# 1-Schematic_hub84_board.net
KiCad netlist of a schematic drawn in EasyEDA
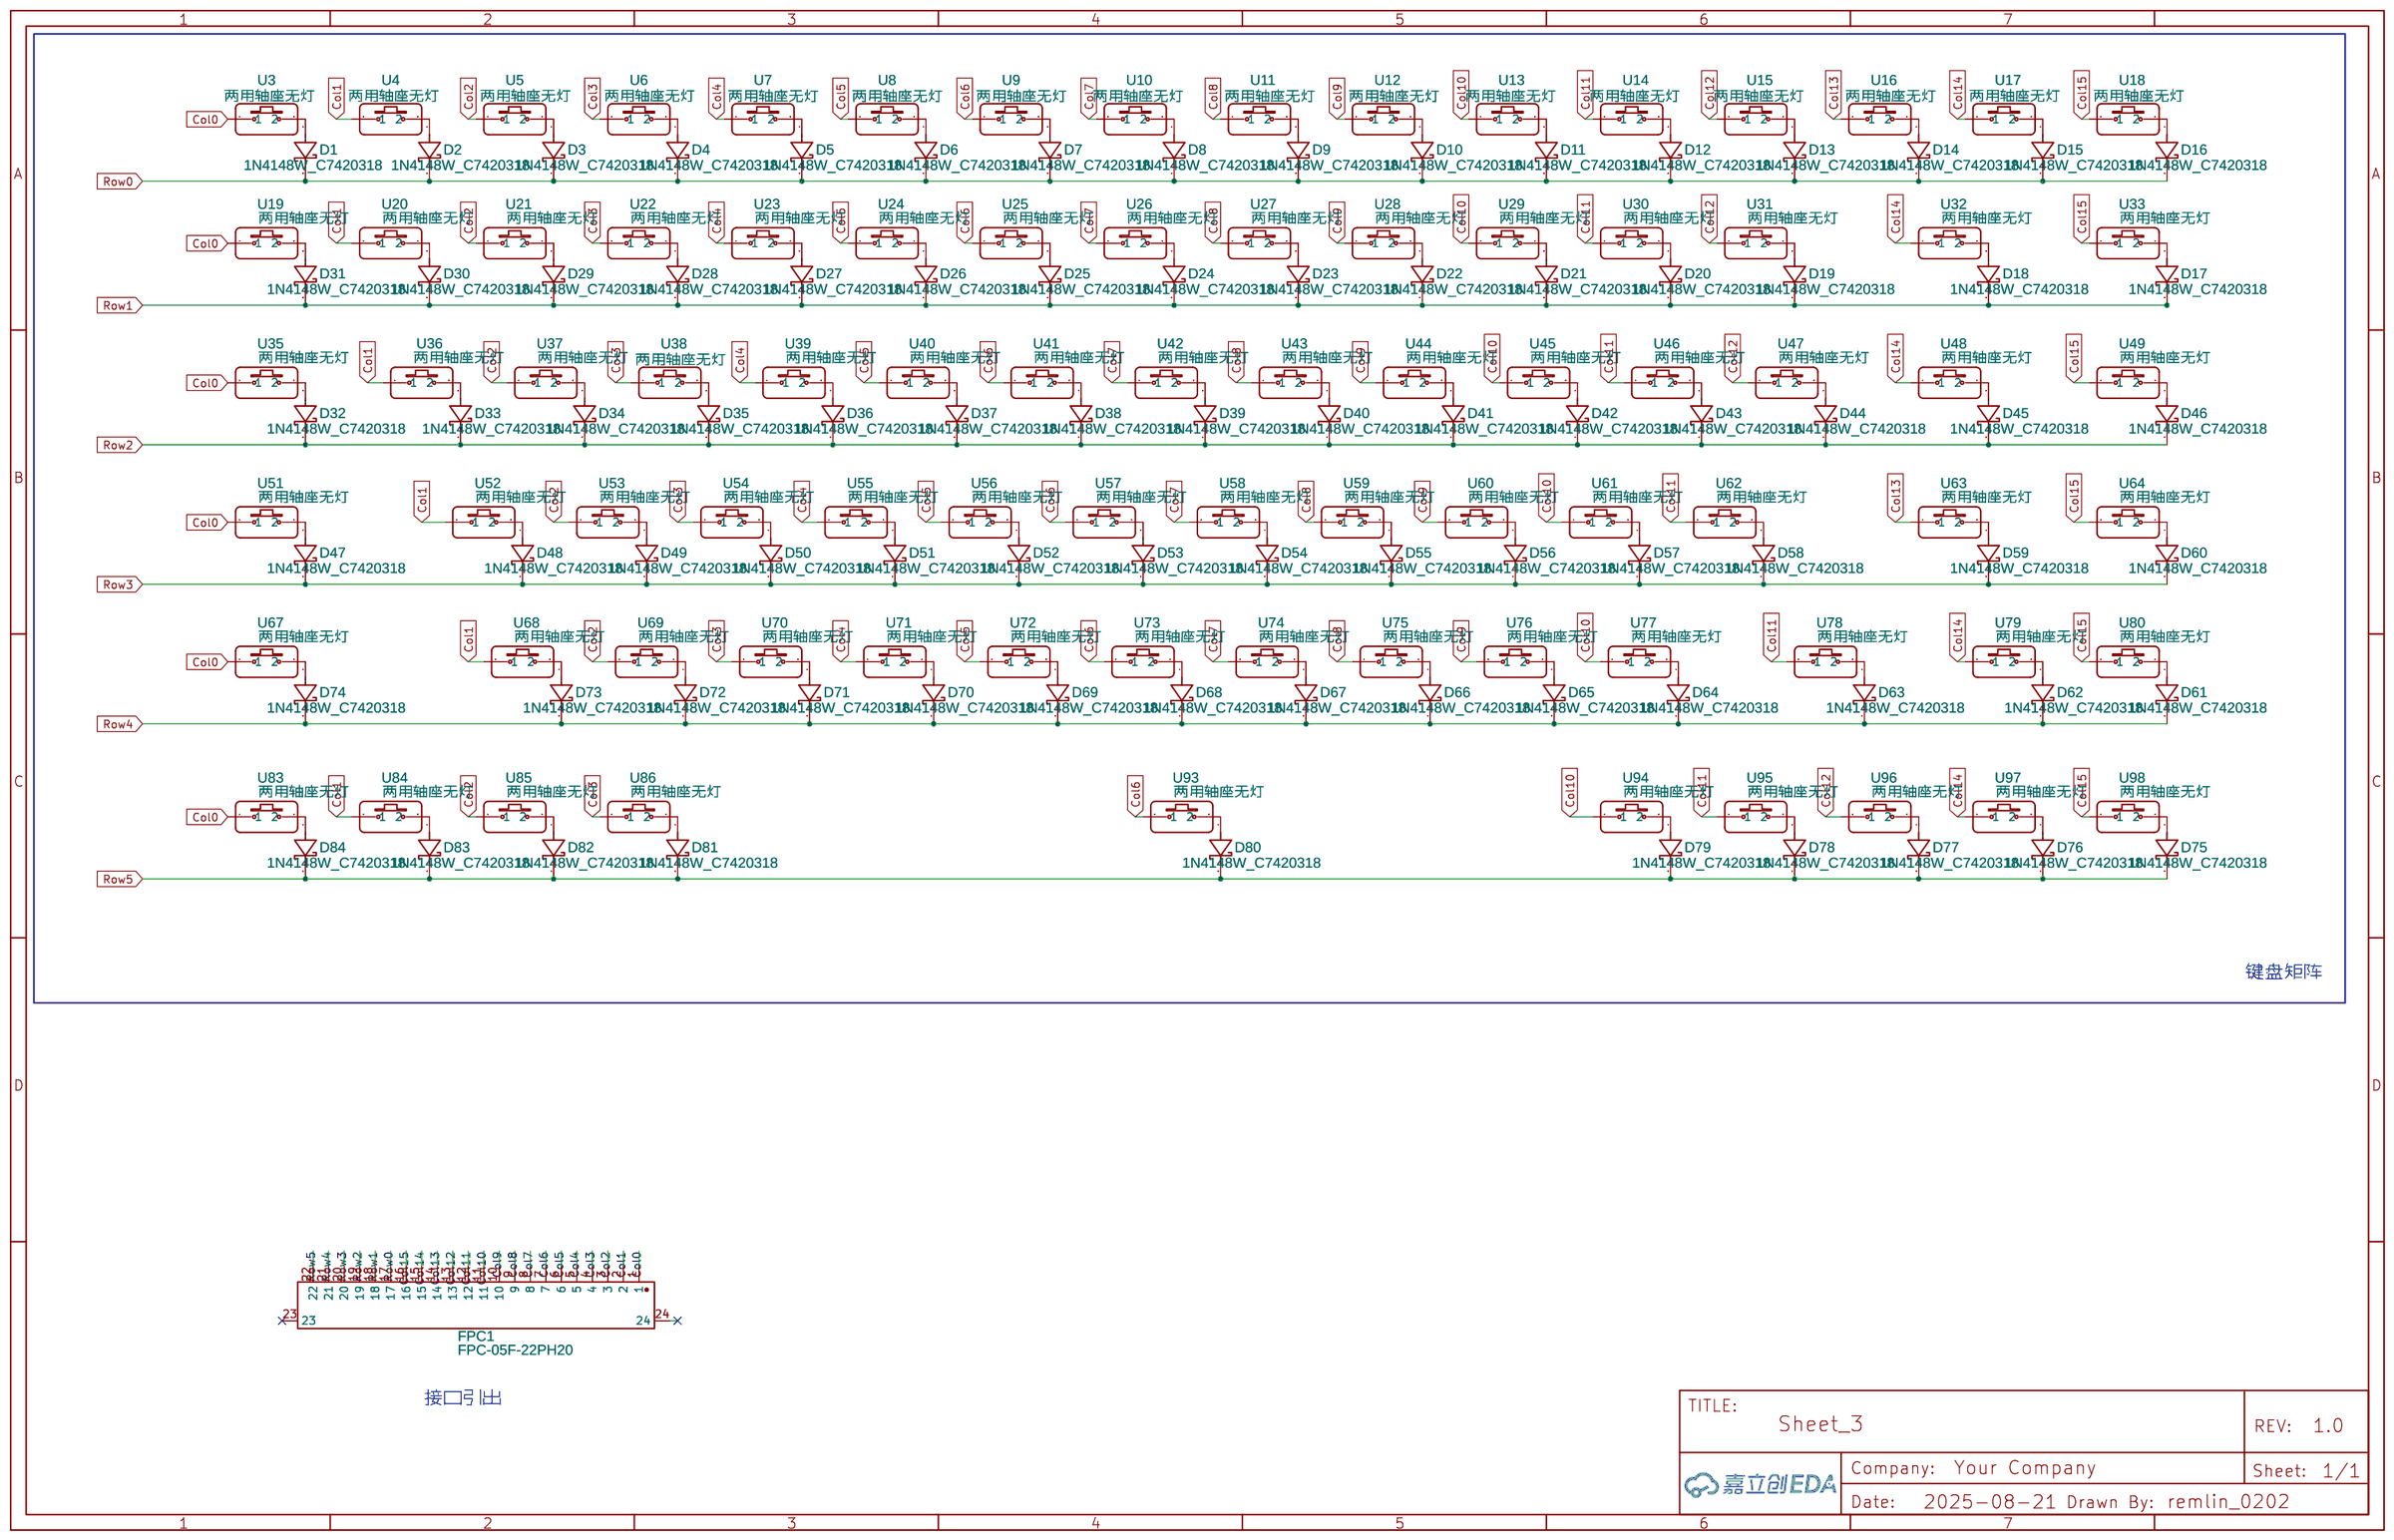
[diagram p0: schematic sheet]

(export (version "E")
  (design (tool "Eeschema 10.0.6"))
  (components
    (comp (ref "D1")
      (value "1N4148W_C7420318")
      (fields (field (name "Manufacturer Part") "1N4148W") (field (name "Manufacturer") "宏嘉诚"))
      (libsource (lib "") (part "1N4148W_C7420318"))
    )
    (comp (ref "D2")
      (value "1N4148W_C7420318")
      (fields (field (name "Manufacturer Part") "1N4148W") (field (name "Manufacturer") "宏嘉诚"))
      (libsource (lib "") (part "1N4148W_C7420318"))
    )
    (comp (ref "D3")
      (value "1N4148W_C7420318")
      (fields (field (name "Manufacturer Part") "1N4148W") (field (name "Manufacturer") "宏嘉诚"))
      (libsource (lib "") (part "1N4148W_C7420318"))
    )
    (comp (ref "D4")
      (value "1N4148W_C7420318")
      (fields (field (name "Manufacturer Part") "1N4148W") (field (name "Manufacturer") "宏嘉诚"))
      (libsource (lib "") (part "1N4148W_C7420318"))
    )
    (comp (ref "D5")
      (value "1N4148W_C7420318")
      (fields (field (name "Manufacturer Part") "1N4148W") (field (name "Manufacturer") "宏嘉诚"))
      (libsource (lib "") (part "1N4148W_C7420318"))
    )
    (comp (ref "D6")
      (value "1N4148W_C7420318")
      (fields (field (name "Manufacturer Part") "1N4148W") (field (name "Manufacturer") "宏嘉诚"))
      (libsource (lib "") (part "1N4148W_C7420318"))
    )
    (comp (ref "D7")
      (value "1N4148W_C7420318")
      (fields (field (name "Manufacturer Part") "1N4148W") (field (name "Manufacturer") "宏嘉诚"))
      (libsource (lib "") (part "1N4148W_C7420318"))
    )
    (comp (ref "D8")
      (value "1N4148W_C7420318")
      (fields (field (name "Manufacturer Part") "1N4148W") (field (name "Manufacturer") "宏嘉诚"))
      (libsource (lib "") (part "1N4148W_C7420318"))
    )
    (comp (ref "D9")
      (value "1N4148W_C7420318")
      (fields (field (name "Manufacturer Part") "1N4148W") (field (name "Manufacturer") "宏嘉诚"))
      (libsource (lib "") (part "1N4148W_C7420318"))
    )
    (comp (ref "D10")
      (value "1N4148W_C7420318")
      (fields (field (name "Manufacturer Part") "1N4148W") (field (name "Manufacturer") "宏嘉诚"))
      (libsource (lib "") (part "1N4148W_C7420318"))
    )
    (comp (ref "D11")
      (value "1N4148W_C7420318")
      (fields (field (name "Manufacturer Part") "1N4148W") (field (name "Manufacturer") "宏嘉诚"))
      (libsource (lib "") (part "1N4148W_C7420318"))
    )
    (comp (ref "D12")
      (value "1N4148W_C7420318")
      (fields (field (name "Manufacturer Part") "1N4148W") (field (name "Manufacturer") "宏嘉诚"))
      (libsource (lib "") (part "1N4148W_C7420318"))
    )
    (comp (ref "D13")
      (value "1N4148W_C7420318")
      (fields (field (name "Manufacturer Part") "1N4148W") (field (name "Manufacturer") "宏嘉诚"))
      (libsource (lib "") (part "1N4148W_C7420318"))
    )
    (comp (ref "D14")
      (value "1N4148W_C7420318")
      (fields (field (name "Manufacturer Part") "1N4148W") (field (name "Manufacturer") "宏嘉诚"))
      (libsource (lib "") (part "1N4148W_C7420318"))
    )
    (comp (ref "D15")
      (value "1N4148W_C7420318")
      (fields (field (name "Manufacturer Part") "1N4148W") (field (name "Manufacturer") "宏嘉诚"))
      (libsource (lib "") (part "1N4148W_C7420318"))
    )
    (comp (ref "D16")
      (value "1N4148W_C7420318")
      (fields (field (name "Manufacturer Part") "1N4148W") (field (name "Manufacturer") "宏嘉诚"))
      (libsource (lib "") (part "1N4148W_C7420318"))
    )
    (comp (ref "D17")
      (value "1N4148W_C7420318")
      (fields (field (name "Manufacturer Part") "1N4148W") (field (name "Manufacturer") "宏嘉诚"))
      (libsource (lib "") (part "1N4148W_C7420318"))
    )
    (comp (ref "D18")
      (value "1N4148W_C7420318")
      (fields (field (name "Manufacturer Part") "1N4148W") (field (name "Manufacturer") "宏嘉诚"))
      (libsource (lib "") (part "1N4148W_C7420318"))
    )
    (comp (ref "D19")
      (value "1N4148W_C7420318")
      (fields (field (name "Manufacturer Part") "1N4148W") (field (name "Manufacturer") "宏嘉诚"))
      (libsource (lib "") (part "1N4148W_C7420318"))
    )
    (comp (ref "D20")
      (value "1N4148W_C7420318")
      (fields (field (name "Manufacturer Part") "1N4148W") (field (name "Manufacturer") "宏嘉诚"))
      (libsource (lib "") (part "1N4148W_C7420318"))
    )
    (comp (ref "D21")
      (value "1N4148W_C7420318")
      (fields (field (name "Manufacturer Part") "1N4148W") (field (name "Manufacturer") "宏嘉诚"))
      (libsource (lib "") (part "1N4148W_C7420318"))
    )
    (comp (ref "D22")
      (value "1N4148W_C7420318")
      (fields (field (name "Manufacturer Part") "1N4148W") (field (name "Manufacturer") "宏嘉诚"))
      (libsource (lib "") (part "1N4148W_C7420318"))
    )
    (comp (ref "D23")
      (value "1N4148W_C7420318")
      (fields (field (name "Manufacturer Part") "1N4148W") (field (name "Manufacturer") "宏嘉诚"))
      (libsource (lib "") (part "1N4148W_C7420318"))
    )
    (comp (ref "D24")
      (value "1N4148W_C7420318")
      (fields (field (name "Manufacturer Part") "1N4148W") (field (name "Manufacturer") "宏嘉诚"))
      (libsource (lib "") (part "1N4148W_C7420318"))
    )
    (comp (ref "D25")
      (value "1N4148W_C7420318")
      (fields (field (name "Manufacturer Part") "1N4148W") (field (name "Manufacturer") "宏嘉诚"))
      (libsource (lib "") (part "1N4148W_C7420318"))
    )
    (comp (ref "D26")
      (value "1N4148W_C7420318")
      (fields (field (name "Manufacturer Part") "1N4148W") (field (name "Manufacturer") "宏嘉诚"))
      (libsource (lib "") (part "1N4148W_C7420318"))
    )
    (comp (ref "D27")
      (value "1N4148W_C7420318")
      (fields (field (name "Manufacturer Part") "1N4148W") (field (name "Manufacturer") "宏嘉诚"))
      (libsource (lib "") (part "1N4148W_C7420318"))
    )
    (comp (ref "D28")
      (value "1N4148W_C7420318")
      (fields (field (name "Manufacturer Part") "1N4148W") (field (name "Manufacturer") "宏嘉诚"))
      (libsource (lib "") (part "1N4148W_C7420318"))
    )
    (comp (ref "D29")
      (value "1N4148W_C7420318")
      (fields (field (name "Manufacturer Part") "1N4148W") (field (name "Manufacturer") "宏嘉诚"))
      (libsource (lib "") (part "1N4148W_C7420318"))
    )
    (comp (ref "D30")
      (value "1N4148W_C7420318")
      (fields (field (name "Manufacturer Part") "1N4148W") (field (name "Manufacturer") "宏嘉诚"))
      (libsource (lib "") (part "1N4148W_C7420318"))
    )
    (comp (ref "D31")
      (value "1N4148W_C7420318")
      (fields (field (name "Manufacturer Part") "1N4148W") (field (name "Manufacturer") "宏嘉诚"))
      (libsource (lib "") (part "1N4148W_C7420318"))
    )
    (comp (ref "D32")
      (value "1N4148W_C7420318")
      (fields (field (name "Manufacturer Part") "1N4148W") (field (name "Manufacturer") "宏嘉诚"))
      (libsource (lib "") (part "1N4148W_C7420318"))
    )
    (comp (ref "D33")
      (value "1N4148W_C7420318")
      (fields (field (name "Manufacturer Part") "1N4148W") (field (name "Manufacturer") "宏嘉诚"))
      (libsource (lib "") (part "1N4148W_C7420318"))
    )
    (comp (ref "D34")
      (value "1N4148W_C7420318")
      (fields (field (name "Manufacturer Part") "1N4148W") (field (name "Manufacturer") "宏嘉诚"))
      (libsource (lib "") (part "1N4148W_C7420318"))
    )
    (comp (ref "D35")
      (value "1N4148W_C7420318")
      (fields (field (name "Manufacturer Part") "1N4148W") (field (name "Manufacturer") "宏嘉诚"))
      (libsource (lib "") (part "1N4148W_C7420318"))
    )
    (comp (ref "D36")
      (value "1N4148W_C7420318")
      (fields (field (name "Manufacturer Part") "1N4148W") (field (name "Manufacturer") "宏嘉诚"))
      (libsource (lib "") (part "1N4148W_C7420318"))
    )
    (comp (ref "D37")
      (value "1N4148W_C7420318")
      (fields (field (name "Manufacturer Part") "1N4148W") (field (name "Manufacturer") "宏嘉诚"))
      (libsource (lib "") (part "1N4148W_C7420318"))
    )
    (comp (ref "D38")
      (value "1N4148W_C7420318")
      (fields (field (name "Manufacturer Part") "1N4148W") (field (name "Manufacturer") "宏嘉诚"))
      (libsource (lib "") (part "1N4148W_C7420318"))
    )
    (comp (ref "D39")
      (value "1N4148W_C7420318")
      (fields (field (name "Manufacturer Part") "1N4148W") (field (name "Manufacturer") "宏嘉诚"))
      (libsource (lib "") (part "1N4148W_C7420318"))
    )
    (comp (ref "D40")
      (value "1N4148W_C7420318")
      (fields (field (name "Manufacturer Part") "1N4148W") (field (name "Manufacturer") "宏嘉诚"))
      (libsource (lib "") (part "1N4148W_C7420318"))
    )
    (comp (ref "D41")
      (value "1N4148W_C7420318")
      (fields (field (name "Manufacturer Part") "1N4148W") (field (name "Manufacturer") "宏嘉诚"))
      (libsource (lib "") (part "1N4148W_C7420318"))
    )
    (comp (ref "D42")
      (value "1N4148W_C7420318")
      (fields (field (name "Manufacturer Part") "1N4148W") (field (name "Manufacturer") "宏嘉诚"))
      (libsource (lib "") (part "1N4148W_C7420318"))
    )
    (comp (ref "D43")
      (value "1N4148W_C7420318")
      (fields (field (name "Manufacturer Part") "1N4148W") (field (name "Manufacturer") "宏嘉诚"))
      (libsource (lib "") (part "1N4148W_C7420318"))
    )
    (comp (ref "D44")
      (value "1N4148W_C7420318")
      (fields (field (name "Manufacturer Part") "1N4148W") (field (name "Manufacturer") "宏嘉诚"))
      (libsource (lib "") (part "1N4148W_C7420318"))
    )
    (comp (ref "D45")
      (value "1N4148W_C7420318")
      (fields (field (name "Manufacturer Part") "1N4148W") (field (name "Manufacturer") "宏嘉诚"))
      (libsource (lib "") (part "1N4148W_C7420318"))
    )
    (comp (ref "D46")
      (value "1N4148W_C7420318")
      (fields (field (name "Manufacturer Part") "1N4148W") (field (name "Manufacturer") "宏嘉诚"))
      (libsource (lib "") (part "1N4148W_C7420318"))
    )
    (comp (ref "D47")
      (value "1N4148W_C7420318")
      (fields (field (name "Manufacturer Part") "1N4148W") (field (name "Manufacturer") "宏嘉诚"))
      (libsource (lib "") (part "1N4148W_C7420318"))
    )
    (comp (ref "D48")
      (value "1N4148W_C7420318")
      (fields (field (name "Manufacturer Part") "1N4148W") (field (name "Manufacturer") "宏嘉诚"))
      (libsource (lib "") (part "1N4148W_C7420318"))
    )
    (comp (ref "D49")
      (value "1N4148W_C7420318")
      (fields (field (name "Manufacturer Part") "1N4148W") (field (name "Manufacturer") "宏嘉诚"))
      (libsource (lib "") (part "1N4148W_C7420318"))
    )
    (comp (ref "D50")
      (value "1N4148W_C7420318")
      (fields (field (name "Manufacturer Part") "1N4148W") (field (name "Manufacturer") "宏嘉诚"))
      (libsource (lib "") (part "1N4148W_C7420318"))
    )
    (comp (ref "D51")
      (value "1N4148W_C7420318")
      (fields (field (name "Manufacturer Part") "1N4148W") (field (name "Manufacturer") "宏嘉诚"))
      (libsource (lib "") (part "1N4148W_C7420318"))
    )
    (comp (ref "D52")
      (value "1N4148W_C7420318")
      (fields (field (name "Manufacturer Part") "1N4148W") (field (name "Manufacturer") "宏嘉诚"))
      (libsource (lib "") (part "1N4148W_C7420318"))
    )
    (comp (ref "D53")
      (value "1N4148W_C7420318")
      (fields (field (name "Manufacturer Part") "1N4148W") (field (name "Manufacturer") "宏嘉诚"))
      (libsource (lib "") (part "1N4148W_C7420318"))
    )
    (comp (ref "D54")
      (value "1N4148W_C7420318")
      (fields (field (name "Manufacturer Part") "1N4148W") (field (name "Manufacturer") "宏嘉诚"))
      (libsource (lib "") (part "1N4148W_C7420318"))
    )
    (comp (ref "D55")
      (value "1N4148W_C7420318")
      (fields (field (name "Manufacturer Part") "1N4148W") (field (name "Manufacturer") "宏嘉诚"))
      (libsource (lib "") (part "1N4148W_C7420318"))
    )
    (comp (ref "D56")
      (value "1N4148W_C7420318")
      (fields (field (name "Manufacturer Part") "1N4148W") (field (name "Manufacturer") "宏嘉诚"))
      (libsource (lib "") (part "1N4148W_C7420318"))
    )
    (comp (ref "D57")
      (value "1N4148W_C7420318")
      (fields (field (name "Manufacturer Part") "1N4148W") (field (name "Manufacturer") "宏嘉诚"))
      (libsource (lib "") (part "1N4148W_C7420318"))
    )
    (comp (ref "D58")
      (value "1N4148W_C7420318")
      (fields (field (name "Manufacturer Part") "1N4148W") (field (name "Manufacturer") "宏嘉诚"))
      (libsource (lib "") (part "1N4148W_C7420318"))
    )
    (comp (ref "D59")
      (value "1N4148W_C7420318")
      (fields (field (name "Manufacturer Part") "1N4148W") (field (name "Manufacturer") "宏嘉诚"))
      (libsource (lib "") (part "1N4148W_C7420318"))
    )
    (comp (ref "D60")
      (value "1N4148W_C7420318")
      (fields (field (name "Manufacturer Part") "1N4148W") (field (name "Manufacturer") "宏嘉诚"))
      (libsource (lib "") (part "1N4148W_C7420318"))
    )
    (comp (ref "D61")
      (value "1N4148W_C7420318")
      (fields (field (name "Manufacturer Part") "1N4148W") (field (name "Manufacturer") "宏嘉诚"))
      (libsource (lib "") (part "1N4148W_C7420318"))
    )
    (comp (ref "D62")
      (value "1N4148W_C7420318")
      (fields (field (name "Manufacturer Part") "1N4148W") (field (name "Manufacturer") "宏嘉诚"))
      (libsource (lib "") (part "1N4148W_C7420318"))
    )
    (comp (ref "D63")
      (value "1N4148W_C7420318")
      (fields (field (name "Manufacturer Part") "1N4148W") (field (name "Manufacturer") "宏嘉诚"))
      (libsource (lib "") (part "1N4148W_C7420318"))
    )
    (comp (ref "D64")
      (value "1N4148W_C7420318")
      (fields (field (name "Manufacturer Part") "1N4148W") (field (name "Manufacturer") "宏嘉诚"))
      (libsource (lib "") (part "1N4148W_C7420318"))
    )
    (comp (ref "D65")
      (value "1N4148W_C7420318")
      (fields (field (name "Manufacturer Part") "1N4148W") (field (name "Manufacturer") "宏嘉诚"))
      (libsource (lib "") (part "1N4148W_C7420318"))
    )
    (comp (ref "D66")
      (value "1N4148W_C7420318")
      (fields (field (name "Manufacturer Part") "1N4148W") (field (name "Manufacturer") "宏嘉诚"))
      (libsource (lib "") (part "1N4148W_C7420318"))
    )
    (comp (ref "D67")
      (value "1N4148W_C7420318")
      (fields (field (name "Manufacturer Part") "1N4148W") (field (name "Manufacturer") "宏嘉诚"))
      (libsource (lib "") (part "1N4148W_C7420318"))
    )
    (comp (ref "D68")
      (value "1N4148W_C7420318")
      (fields (field (name "Manufacturer Part") "1N4148W") (field (name "Manufacturer") "宏嘉诚"))
      (libsource (lib "") (part "1N4148W_C7420318"))
    )
    (comp (ref "D69")
      (value "1N4148W_C7420318")
      (fields (field (name "Manufacturer Part") "1N4148W") (field (name "Manufacturer") "宏嘉诚"))
      (libsource (lib "") (part "1N4148W_C7420318"))
    )
    (comp (ref "D70")
      (value "1N4148W_C7420318")
      (fields (field (name "Manufacturer Part") "1N4148W") (field (name "Manufacturer") "宏嘉诚"))
      (libsource (lib "") (part "1N4148W_C7420318"))
    )
    (comp (ref "D71")
      (value "1N4148W_C7420318")
      (fields (field (name "Manufacturer Part") "1N4148W") (field (name "Manufacturer") "宏嘉诚"))
      (libsource (lib "") (part "1N4148W_C7420318"))
    )
    (comp (ref "D72")
      (value "1N4148W_C7420318")
      (fields (field (name "Manufacturer Part") "1N4148W") (field (name "Manufacturer") "宏嘉诚"))
      (libsource (lib "") (part "1N4148W_C7420318"))
    )
    (comp (ref "D73")
      (value "1N4148W_C7420318")
      (fields (field (name "Manufacturer Part") "1N4148W") (field (name "Manufacturer") "宏嘉诚"))
      (libsource (lib "") (part "1N4148W_C7420318"))
    )
    (comp (ref "D74")
      (value "1N4148W_C7420318")
      (fields (field (name "Manufacturer Part") "1N4148W") (field (name "Manufacturer") "宏嘉诚"))
      (libsource (lib "") (part "1N4148W_C7420318"))
    )
    (comp (ref "D75")
      (value "1N4148W_C7420318")
      (fields (field (name "Manufacturer Part") "1N4148W") (field (name "Manufacturer") "宏嘉诚"))
      (libsource (lib "") (part "1N4148W_C7420318"))
    )
    (comp (ref "D76")
      (value "1N4148W_C7420318")
      (fields (field (name "Manufacturer Part") "1N4148W") (field (name "Manufacturer") "宏嘉诚"))
      (libsource (lib "") (part "1N4148W_C7420318"))
    )
    (comp (ref "D77")
      (value "1N4148W_C7420318")
      (fields (field (name "Manufacturer Part") "1N4148W") (field (name "Manufacturer") "宏嘉诚"))
      (libsource (lib "") (part "1N4148W_C7420318"))
    )
    (comp (ref "D78")
      (value "1N4148W_C7420318")
      (fields (field (name "Manufacturer Part") "1N4148W") (field (name "Manufacturer") "宏嘉诚"))
      (libsource (lib "") (part "1N4148W_C7420318"))
    )
    (comp (ref "D79")
      (value "1N4148W_C7420318")
      (fields (field (name "Manufacturer Part") "1N4148W") (field (name "Manufacturer") "宏嘉诚"))
      (libsource (lib "") (part "1N4148W_C7420318"))
    )
    (comp (ref "D80")
      (value "1N4148W_C7420318")
      (fields (field (name "Manufacturer Part") "1N4148W") (field (name "Manufacturer") "宏嘉诚"))
      (libsource (lib "") (part "1N4148W_C7420318"))
    )
    (comp (ref "D81")
      (value "1N4148W_C7420318")
      (fields (field (name "Manufacturer Part") "1N4148W") (field (name "Manufacturer") "宏嘉诚"))
      (libsource (lib "") (part "1N4148W_C7420318"))
    )
    (comp (ref "D82")
      (value "1N4148W_C7420318")
      (fields (field (name "Manufacturer Part") "1N4148W") (field (name "Manufacturer") "宏嘉诚"))
      (libsource (lib "") (part "1N4148W_C7420318"))
    )
    (comp (ref "D83")
      (value "1N4148W_C7420318")
      (fields (field (name "Manufacturer Part") "1N4148W") (field (name "Manufacturer") "宏嘉诚"))
      (libsource (lib "") (part "1N4148W_C7420318"))
    )
    (comp (ref "D84")
      (value "1N4148W_C7420318")
      (fields (field (name "Manufacturer Part") "1N4148W") (field (name "Manufacturer") "宏嘉诚"))
      (libsource (lib "") (part "1N4148W_C7420318"))
    )
    (comp (ref "FPC1")
      (value "FPC-05F-22PH20")
      (fields (field (name "Manufacturer") "XUNPU(讯普)"))
      (libsource (lib "") (part "FPC-05F-22PH20"))
    )
    (comp (ref "U3") (value "两用轴座无灯") (libsource (lib "") (part "两用轴座无灯")))
    (comp (ref "U4") (value "两用轴座无灯") (libsource (lib "") (part "两用轴座无灯")))
    (comp (ref "U5") (value "两用轴座无灯") (libsource (lib "") (part "两用轴座无灯")))
    (comp (ref "U6") (value "两用轴座无灯") (libsource (lib "") (part "两用轴座无灯")))
    (comp (ref "U7") (value "两用轴座无灯") (libsource (lib "") (part "两用轴座无灯")))
    (comp (ref "U8") (value "两用轴座无灯") (libsource (lib "") (part "两用轴座无灯")))
    (comp (ref "U9") (value "两用轴座无灯") (libsource (lib "") (part "两用轴座无灯")))
    (comp (ref "U10") (value "两用轴座无灯") (libsource (lib "") (part "两用轴座无灯")))
    (comp (ref "U11") (value "两用轴座无灯") (libsource (lib "") (part "两用轴座无灯")))
    (comp (ref "U12") (value "两用轴座无灯") (libsource (lib "") (part "两用轴座无灯")))
    (comp (ref "U13") (value "两用轴座无灯") (libsource (lib "") (part "两用轴座无灯")))
    (comp (ref "U14") (value "两用轴座无灯") (libsource (lib "") (part "两用轴座无灯")))
    (comp (ref "U15") (value "两用轴座无灯") (libsource (lib "") (part "两用轴座无灯")))
    (comp (ref "U16") (value "两用轴座无灯") (libsource (lib "") (part "两用轴座无灯")))
    (comp (ref "U17") (value "两用轴座无灯") (libsource (lib "") (part "两用轴座无灯")))
    (comp (ref "U18") (value "两用轴座无灯") (libsource (lib "") (part "两用轴座无灯")))
    (comp (ref "U19") (value "两用轴座无灯") (libsource (lib "") (part "两用轴座无灯")))
    (comp (ref "U20") (value "两用轴座无灯") (libsource (lib "") (part "两用轴座无灯")))
    (comp (ref "U21") (value "两用轴座无灯") (libsource (lib "") (part "两用轴座无灯")))
    (comp (ref "U22") (value "两用轴座无灯") (libsource (lib "") (part "两用轴座无灯")))
    (comp (ref "U23") (value "两用轴座无灯") (libsource (lib "") (part "两用轴座无灯")))
    (comp (ref "U24") (value "两用轴座无灯") (libsource (lib "") (part "两用轴座无灯")))
    (comp (ref "U25") (value "两用轴座无灯") (libsource (lib "") (part "两用轴座无灯")))
    (comp (ref "U26") (value "两用轴座无灯") (libsource (lib "") (part "两用轴座无灯")))
    (comp (ref "U27") (value "两用轴座无灯") (libsource (lib "") (part "两用轴座无灯")))
    (comp (ref "U28") (value "两用轴座无灯") (libsource (lib "") (part "两用轴座无灯")))
    (comp (ref "U29") (value "两用轴座无灯") (libsource (lib "") (part "两用轴座无灯")))
    (comp (ref "U30") (value "两用轴座无灯") (libsource (lib "") (part "两用轴座无灯")))
    (comp (ref "U31") (value "两用轴座无灯") (libsource (lib "") (part "两用轴座无灯")))
    (comp (ref "U32") (value "两用轴座无灯") (libsource (lib "") (part "两用轴座无灯")))
    (comp (ref "U33") (value "两用轴座无灯") (libsource (lib "") (part "两用轴座无灯")))
    (comp (ref "U35") (value "两用轴座无灯") (libsource (lib "") (part "两用轴座无灯")))
    (comp (ref "U36") (value "两用轴座无灯") (libsource (lib "") (part "两用轴座无灯")))
    (comp (ref "U37") (value "两用轴座无灯") (libsource (lib "") (part "两用轴座无灯")))
    (comp (ref "U38") (value "两用轴座无灯") (libsource (lib "") (part "两用轴座无灯")))
    (comp (ref "U39") (value "两用轴座无灯") (libsource (lib "") (part "两用轴座无灯")))
    (comp (ref "U40") (value "两用轴座无灯") (libsource (lib "") (part "两用轴座无灯")))
    (comp (ref "U41") (value "两用轴座无灯") (libsource (lib "") (part "两用轴座无灯")))
    (comp (ref "U42") (value "两用轴座无灯") (libsource (lib "") (part "两用轴座无灯")))
    (comp (ref "U43") (value "两用轴座无灯") (libsource (lib "") (part "两用轴座无灯")))
    (comp (ref "U44") (value "两用轴座无灯") (libsource (lib "") (part "两用轴座无灯")))
    (comp (ref "U45") (value "两用轴座无灯") (libsource (lib "") (part "两用轴座无灯")))
    (comp (ref "U46") (value "两用轴座无灯") (libsource (lib "") (part "两用轴座无灯")))
    (comp (ref "U47") (value "两用轴座无灯") (libsource (lib "") (part "两用轴座无灯")))
    (comp (ref "U48") (value "两用轴座无灯") (libsource (lib "") (part "两用轴座无灯")))
    (comp (ref "U49") (value "两用轴座无灯") (libsource (lib "") (part "两用轴座无灯")))
    (comp (ref "U51") (value "两用轴座无灯") (libsource (lib "") (part "两用轴座无灯")))
    (comp (ref "U52") (value "两用轴座无灯") (libsource (lib "") (part "两用轴座无灯")))
    (comp (ref "U53") (value "两用轴座无灯") (libsource (lib "") (part "两用轴座无灯")))
    (comp (ref "U54") (value "两用轴座无灯") (libsource (lib "") (part "两用轴座无灯")))
    (comp (ref "U55") (value "两用轴座无灯") (libsource (lib "") (part "两用轴座无灯")))
    (comp (ref "U56") (value "两用轴座无灯") (libsource (lib "") (part "两用轴座无灯")))
    (comp (ref "U57") (value "两用轴座无灯") (libsource (lib "") (part "两用轴座无灯")))
    (comp (ref "U58") (value "两用轴座无灯") (libsource (lib "") (part "两用轴座无灯")))
    (comp (ref "U59") (value "两用轴座无灯") (libsource (lib "") (part "两用轴座无灯")))
    (comp (ref "U60") (value "两用轴座无灯") (libsource (lib "") (part "两用轴座无灯")))
    (comp (ref "U61") (value "两用轴座无灯") (libsource (lib "") (part "两用轴座无灯")))
    (comp (ref "U62") (value "两用轴座无灯") (libsource (lib "") (part "两用轴座无灯")))
    (comp (ref "U63") (value "两用轴座无灯") (libsource (lib "") (part "两用轴座无灯")))
    (comp (ref "U64") (value "两用轴座无灯") (libsource (lib "") (part "两用轴座无灯")))
    (comp (ref "U67") (value "两用轴座无灯") (libsource (lib "") (part "两用轴座无灯")))
    (comp (ref "U68") (value "两用轴座无灯") (libsource (lib "") (part "两用轴座无灯")))
    (comp (ref "U69") (value "两用轴座无灯") (libsource (lib "") (part "两用轴座无灯")))
    (comp (ref "U70") (value "两用轴座无灯") (libsource (lib "") (part "两用轴座无灯")))
    (comp (ref "U71") (value "两用轴座无灯") (libsource (lib "") (part "两用轴座无灯")))
    (comp (ref "U72") (value "两用轴座无灯") (libsource (lib "") (part "两用轴座无灯")))
    (comp (ref "U73") (value "两用轴座无灯") (libsource (lib "") (part "两用轴座无灯")))
    (comp (ref "U74") (value "两用轴座无灯") (libsource (lib "") (part "两用轴座无灯")))
    (comp (ref "U75") (value "两用轴座无灯") (libsource (lib "") (part "两用轴座无灯")))
    (comp (ref "U76") (value "两用轴座无灯") (libsource (lib "") (part "两用轴座无灯")))
    (comp (ref "U77") (value "两用轴座无灯") (libsource (lib "") (part "两用轴座无灯")))
    (comp (ref "U78") (value "两用轴座无灯") (libsource (lib "") (part "两用轴座无灯")))
    (comp (ref "U79") (value "两用轴座无灯") (libsource (lib "") (part "两用轴座无灯")))
    (comp (ref "U80") (value "两用轴座无灯") (libsource (lib "") (part "两用轴座无灯")))
    (comp (ref "U83") (value "两用轴座无灯") (libsource (lib "") (part "两用轴座无灯")))
    (comp (ref "U84") (value "两用轴座无灯") (libsource (lib "") (part "两用轴座无灯")))
    (comp (ref "U85") (value "两用轴座无灯") (libsource (lib "") (part "两用轴座无灯")))
    (comp (ref "U86") (value "两用轴座无灯") (libsource (lib "") (part "两用轴座无灯")))
    (comp (ref "U93") (value "两用轴座无灯") (libsource (lib "") (part "两用轴座无灯")))
    (comp (ref "U94") (value "两用轴座无灯") (libsource (lib "") (part "两用轴座无灯")))
    (comp (ref "U95") (value "两用轴座无灯") (libsource (lib "") (part "两用轴座无灯")))
    (comp (ref "U96") (value "两用轴座无灯") (libsource (lib "") (part "两用轴座无灯")))
    (comp (ref "U97") (value "两用轴座无灯") (libsource (lib "") (part "两用轴座无灯")))
    (comp (ref "U98") (value "两用轴座无灯") (libsource (lib "") (part "两用轴座无灯")))
  )
  (nets
    (net (code "1") (name "Col0") (class "Default")
      (node (ref "FPC1") (pin "1") (pinfunction "1_1") (pintype "unspecified"))
      (node (ref "U19") (pin "1") (pinfunction "1_1") (pintype "unspecified"))
      (node (ref "U3") (pin "1") (pinfunction "1_1") (pintype "unspecified"))
      (node (ref "U35") (pin "1") (pinfunction "1_1") (pintype "unspecified"))
      (node (ref "U51") (pin "1") (pinfunction "1_1") (pintype "unspecified"))
      (node (ref "U67") (pin "1") (pinfunction "1_1") (pintype "unspecified"))
      (node (ref "U83") (pin "1") (pinfunction "1_1") (pintype "unspecified"))
    )
    (net (code "2") (name "Col1") (class "Default")
      (node (ref "FPC1") (pin "2") (pinfunction "2_2") (pintype "unspecified"))
      (node (ref "U20") (pin "1") (pinfunction "1_1") (pintype "unspecified"))
      (node (ref "U36") (pin "1") (pinfunction "1_1") (pintype "unspecified"))
      (node (ref "U4") (pin "1") (pinfunction "1_1") (pintype "unspecified"))
      (node (ref "U52") (pin "1") (pinfunction "1_1") (pintype "unspecified"))
      (node (ref "U68") (pin "1") (pinfunction "1_1") (pintype "unspecified"))
      (node (ref "U84") (pin "1") (pinfunction "1_1") (pintype "unspecified"))
    )
    (net (code "3") (name "Col2") (class "Default")
      (node (ref "FPC1") (pin "3") (pinfunction "3_3") (pintype "unspecified"))
      (node (ref "U21") (pin "1") (pinfunction "1_1") (pintype "unspecified"))
      (node (ref "U37") (pin "1") (pinfunction "1_1") (pintype "unspecified"))
      (node (ref "U5") (pin "1") (pinfunction "1_1") (pintype "unspecified"))
      (node (ref "U53") (pin "1") (pinfunction "1_1") (pintype "unspecified"))
      (node (ref "U69") (pin "1") (pinfunction "1_1") (pintype "unspecified"))
      (node (ref "U85") (pin "1") (pinfunction "1_1") (pintype "unspecified"))
    )
    (net (code "4") (name "Col3") (class "Default")
      (node (ref "FPC1") (pin "4") (pinfunction "4_4") (pintype "unspecified"))
      (node (ref "U22") (pin "1") (pinfunction "1_1") (pintype "unspecified"))
      (node (ref "U38") (pin "1") (pinfunction "1_1") (pintype "unspecified"))
      (node (ref "U54") (pin "1") (pinfunction "1_1") (pintype "unspecified"))
      (node (ref "U6") (pin "1") (pinfunction "1_1") (pintype "unspecified"))
      (node (ref "U70") (pin "1") (pinfunction "1_1") (pintype "unspecified"))
      (node (ref "U86") (pin "1") (pinfunction "1_1") (pintype "unspecified"))
    )
    (net (code "5") (name "Col4") (class "Default")
      (node (ref "FPC1") (pin "5") (pinfunction "5_5") (pintype "unspecified"))
      (node (ref "U23") (pin "1") (pinfunction "1_1") (pintype "unspecified"))
      (node (ref "U39") (pin "1") (pinfunction "1_1") (pintype "unspecified"))
      (node (ref "U55") (pin "1") (pinfunction "1_1") (pintype "unspecified"))
      (node (ref "U7") (pin "1") (pinfunction "1_1") (pintype "unspecified"))
      (node (ref "U71") (pin "1") (pinfunction "1_1") (pintype "unspecified"))
    )
    (net (code "6") (name "Col5") (class "Default")
      (node (ref "FPC1") (pin "6") (pinfunction "6_6") (pintype "unspecified"))
      (node (ref "U24") (pin "1") (pinfunction "1_1") (pintype "unspecified"))
      (node (ref "U40") (pin "1") (pinfunction "1_1") (pintype "unspecified"))
      (node (ref "U56") (pin "1") (pinfunction "1_1") (pintype "unspecified"))
      (node (ref "U72") (pin "1") (pinfunction "1_1") (pintype "unspecified"))
      (node (ref "U8") (pin "1") (pinfunction "1_1") (pintype "unspecified"))
    )
    (net (code "7") (name "Col6") (class "Default")
      (node (ref "FPC1") (pin "7") (pinfunction "7_7") (pintype "unspecified"))
      (node (ref "U25") (pin "1") (pinfunction "1_1") (pintype "unspecified"))
      (node (ref "U41") (pin "1") (pinfunction "1_1") (pintype "unspecified"))
      (node (ref "U57") (pin "1") (pinfunction "1_1") (pintype "unspecified"))
      (node (ref "U73") (pin "1") (pinfunction "1_1") (pintype "unspecified"))
      (node (ref "U9") (pin "1") (pinfunction "1_1") (pintype "unspecified"))
      (node (ref "U93") (pin "1") (pinfunction "1_1") (pintype "unspecified"))
    )
    (net (code "8") (name "Col7") (class "Default")
      (node (ref "FPC1") (pin "8") (pinfunction "8_8") (pintype "unspecified"))
      (node (ref "U10") (pin "1") (pinfunction "1_1") (pintype "unspecified"))
      (node (ref "U26") (pin "1") (pinfunction "1_1") (pintype "unspecified"))
      (node (ref "U42") (pin "1") (pinfunction "1_1") (pintype "unspecified"))
      (node (ref "U58") (pin "1") (pinfunction "1_1") (pintype "unspecified"))
      (node (ref "U74") (pin "1") (pinfunction "1_1") (pintype "unspecified"))
    )
    (net (code "9") (name "Col8") (class "Default")
      (node (ref "FPC1") (pin "9") (pinfunction "9_9") (pintype "unspecified"))
      (node (ref "U11") (pin "1") (pinfunction "1_1") (pintype "unspecified"))
      (node (ref "U27") (pin "1") (pinfunction "1_1") (pintype "unspecified"))
      (node (ref "U43") (pin "1") (pinfunction "1_1") (pintype "unspecified"))
      (node (ref "U59") (pin "1") (pinfunction "1_1") (pintype "unspecified"))
      (node (ref "U75") (pin "1") (pinfunction "1_1") (pintype "unspecified"))
    )
    (net (code "10") (name "Col9") (class "Default")
      (node (ref "FPC1") (pin "10") (pinfunction "10_10") (pintype "unspecified"))
      (node (ref "U12") (pin "1") (pinfunction "1_1") (pintype "unspecified"))
      (node (ref "U28") (pin "1") (pinfunction "1_1") (pintype "unspecified"))
      (node (ref "U44") (pin "1") (pinfunction "1_1") (pintype "unspecified"))
      (node (ref "U60") (pin "1") (pinfunction "1_1") (pintype "unspecified"))
      (node (ref "U76") (pin "1") (pinfunction "1_1") (pintype "unspecified"))
    )
    (net (code "11") (name "Col10") (class "Default")
      (node (ref "FPC1") (pin "11") (pinfunction "11_11") (pintype "unspecified"))
      (node (ref "U13") (pin "1") (pinfunction "1_1") (pintype "unspecified"))
      (node (ref "U29") (pin "1") (pinfunction "1_1") (pintype "unspecified"))
      (node (ref "U45") (pin "1") (pinfunction "1_1") (pintype "unspecified"))
      (node (ref "U61") (pin "1") (pinfunction "1_1") (pintype "unspecified"))
      (node (ref "U77") (pin "1") (pinfunction "1_1") (pintype "unspecified"))
      (node (ref "U94") (pin "1") (pinfunction "1_1") (pintype "unspecified"))
    )
    (net (code "12") (name "Col11") (class "Default")
      (node (ref "FPC1") (pin "12") (pinfunction "12_12") (pintype "unspecified"))
      (node (ref "U14") (pin "1") (pinfunction "1_1") (pintype "unspecified"))
      (node (ref "U30") (pin "1") (pinfunction "1_1") (pintype "unspecified"))
      (node (ref "U46") (pin "1") (pinfunction "1_1") (pintype "unspecified"))
      (node (ref "U62") (pin "1") (pinfunction "1_1") (pintype "unspecified"))
      (node (ref "U78") (pin "1") (pinfunction "1_1") (pintype "unspecified"))
      (node (ref "U95") (pin "1") (pinfunction "1_1") (pintype "unspecified"))
    )
    (net (code "13") (name "Col12") (class "Default")
      (node (ref "FPC1") (pin "13") (pinfunction "13_13") (pintype "unspecified"))
      (node (ref "U15") (pin "1") (pinfunction "1_1") (pintype "unspecified"))
      (node (ref "U31") (pin "1") (pinfunction "1_1") (pintype "unspecified"))
      (node (ref "U47") (pin "1") (pinfunction "1_1") (pintype "unspecified"))
      (node (ref "U96") (pin "1") (pinfunction "1_1") (pintype "unspecified"))
    )
    (net (code "14") (name "Col13") (class "Default")
      (node (ref "FPC1") (pin "14") (pinfunction "14_14") (pintype "unspecified"))
      (node (ref "U16") (pin "1") (pinfunction "1_1") (pintype "unspecified"))
      (node (ref "U63") (pin "1") (pinfunction "1_1") (pintype "unspecified"))
    )
    (net (code "15") (name "Col14") (class "Default")
      (node (ref "FPC1") (pin "15") (pinfunction "15_15") (pintype "unspecified"))
      (node (ref "U17") (pin "1") (pinfunction "1_1") (pintype "unspecified"))
      (node (ref "U32") (pin "1") (pinfunction "1_1") (pintype "unspecified"))
      (node (ref "U48") (pin "1") (pinfunction "1_1") (pintype "unspecified"))
      (node (ref "U79") (pin "1") (pinfunction "1_1") (pintype "unspecified"))
      (node (ref "U97") (pin "1") (pinfunction "1_1") (pintype "unspecified"))
    )
    (net (code "16") (name "Col15") (class "Default")
      (node (ref "FPC1") (pin "16") (pinfunction "16_16") (pintype "unspecified"))
      (node (ref "U18") (pin "1") (pinfunction "1_1") (pintype "unspecified"))
      (node (ref "U33") (pin "1") (pinfunction "1_1") (pintype "unspecified"))
      (node (ref "U49") (pin "1") (pinfunction "1_1") (pintype "unspecified"))
      (node (ref "U64") (pin "1") (pinfunction "1_1") (pintype "unspecified"))
      (node (ref "U80") (pin "1") (pinfunction "1_1") (pintype "unspecified"))
      (node (ref "U98") (pin "1") (pinfunction "1_1") (pintype "unspecified"))
    )
    (net (code "17") (name "Net-(D1-A)") (class "Default")
      (node (ref "D1") (pin "1") (pinfunction "A_1") (pintype "unspecified"))
      (node (ref "U3") (pin "2") (pinfunction "2_2") (pintype "unspecified"))
    )
    (net (code "18") (name "Net-(D2-A)") (class "Default")
      (node (ref "D2") (pin "1") (pinfunction "A_1") (pintype "unspecified"))
      (node (ref "U4") (pin "2") (pinfunction "2_2") (pintype "unspecified"))
    )
    (net (code "19") (name "Net-(D3-A)") (class "Default")
      (node (ref "D3") (pin "1") (pinfunction "A_1") (pintype "unspecified"))
      (node (ref "U5") (pin "2") (pinfunction "2_2") (pintype "unspecified"))
    )
    (net (code "20") (name "Net-(D4-A)") (class "Default")
      (node (ref "D4") (pin "1") (pinfunction "A_1") (pintype "unspecified"))
      (node (ref "U6") (pin "2") (pinfunction "2_2") (pintype "unspecified"))
    )
    (net (code "21") (name "Net-(D5-A)") (class "Default")
      (node (ref "D5") (pin "1") (pinfunction "A_1") (pintype "unspecified"))
      (node (ref "U7") (pin "2") (pinfunction "2_2") (pintype "unspecified"))
    )
    (net (code "22") (name "Net-(D6-A)") (class "Default")
      (node (ref "D6") (pin "1") (pinfunction "A_1") (pintype "unspecified"))
      (node (ref "U8") (pin "2") (pinfunction "2_2") (pintype "unspecified"))
    )
    (net (code "23") (name "Net-(D7-A)") (class "Default")
      (node (ref "D7") (pin "1") (pinfunction "A_1") (pintype "unspecified"))
      (node (ref "U9") (pin "2") (pinfunction "2_2") (pintype "unspecified"))
    )
    (net (code "24") (name "Net-(D8-A)") (class "Default")
      (node (ref "D8") (pin "1") (pinfunction "A_1") (pintype "unspecified"))
      (node (ref "U10") (pin "2") (pinfunction "2_2") (pintype "unspecified"))
    )
    (net (code "25") (name "Net-(D9-A)") (class "Default")
      (node (ref "D9") (pin "1") (pinfunction "A_1") (pintype "unspecified"))
      (node (ref "U11") (pin "2") (pinfunction "2_2") (pintype "unspecified"))
    )
    (net (code "26") (name "Net-(D10-A)") (class "Default")
      (node (ref "D10") (pin "1") (pinfunction "A_1") (pintype "unspecified"))
      (node (ref "U12") (pin "2") (pinfunction "2_2") (pintype "unspecified"))
    )
    (net (code "27") (name "Net-(D11-A)") (class "Default")
      (node (ref "D11") (pin "1") (pinfunction "A_1") (pintype "unspecified"))
      (node (ref "U13") (pin "2") (pinfunction "2_2") (pintype "unspecified"))
    )
    (net (code "28") (name "Net-(D12-A)") (class "Default")
      (node (ref "D12") (pin "1") (pinfunction "A_1") (pintype "unspecified"))
      (node (ref "U14") (pin "2") (pinfunction "2_2") (pintype "unspecified"))
    )
    (net (code "29") (name "Net-(D13-A)") (class "Default")
      (node (ref "D13") (pin "1") (pinfunction "A_1") (pintype "unspecified"))
      (node (ref "U15") (pin "2") (pinfunction "2_2") (pintype "unspecified"))
    )
    (net (code "30") (name "Net-(D14-A)") (class "Default")
      (node (ref "D14") (pin "1") (pinfunction "A_1") (pintype "unspecified"))
      (node (ref "U16") (pin "2") (pinfunction "2_2") (pintype "unspecified"))
    )
    (net (code "31") (name "Net-(D15-A)") (class "Default")
      (node (ref "D15") (pin "1") (pinfunction "A_1") (pintype "unspecified"))
      (node (ref "U17") (pin "2") (pinfunction "2_2") (pintype "unspecified"))
    )
    (net (code "32") (name "Net-(D16-A)") (class "Default")
      (node (ref "D16") (pin "1") (pinfunction "A_1") (pintype "unspecified"))
      (node (ref "U18") (pin "2") (pinfunction "2_2") (pintype "unspecified"))
    )
    (net (code "33") (name "Net-(D17-A)") (class "Default")
      (node (ref "D17") (pin "1") (pinfunction "A_1") (pintype "unspecified"))
      (node (ref "U33") (pin "2") (pinfunction "2_2") (pintype "unspecified"))
    )
    (net (code "34") (name "Net-(D18-A)") (class "Default")
      (node (ref "D18") (pin "1") (pinfunction "A_1") (pintype "unspecified"))
      (node (ref "U32") (pin "2") (pinfunction "2_2") (pintype "unspecified"))
    )
    (net (code "35") (name "Net-(D19-A)") (class "Default")
      (node (ref "D19") (pin "1") (pinfunction "A_1") (pintype "unspecified"))
      (node (ref "U31") (pin "2") (pinfunction "2_2") (pintype "unspecified"))
    )
    (net (code "36") (name "Net-(D20-A)") (class "Default")
      (node (ref "D20") (pin "1") (pinfunction "A_1") (pintype "unspecified"))
      (node (ref "U30") (pin "2") (pinfunction "2_2") (pintype "unspecified"))
    )
    (net (code "37") (name "Net-(D21-A)") (class "Default")
      (node (ref "D21") (pin "1") (pinfunction "A_1") (pintype "unspecified"))
      (node (ref "U29") (pin "2") (pinfunction "2_2") (pintype "unspecified"))
    )
    (net (code "38") (name "Net-(D22-A)") (class "Default")
      (node (ref "D22") (pin "1") (pinfunction "A_1") (pintype "unspecified"))
      (node (ref "U28") (pin "2") (pinfunction "2_2") (pintype "unspecified"))
    )
    (net (code "39") (name "Net-(D23-A)") (class "Default")
      (node (ref "D23") (pin "1") (pinfunction "A_1") (pintype "unspecified"))
      (node (ref "U27") (pin "2") (pinfunction "2_2") (pintype "unspecified"))
    )
    (net (code "40") (name "Net-(D24-A)") (class "Default")
      (node (ref "D24") (pin "1") (pinfunction "A_1") (pintype "unspecified"))
      (node (ref "U26") (pin "2") (pinfunction "2_2") (pintype "unspecified"))
    )
    (net (code "41") (name "Net-(D25-A)") (class "Default")
      (node (ref "D25") (pin "1") (pinfunction "A_1") (pintype "unspecified"))
      (node (ref "U25") (pin "2") (pinfunction "2_2") (pintype "unspecified"))
    )
    (net (code "42") (name "Net-(D26-A)") (class "Default")
      (node (ref "D26") (pin "1") (pinfunction "A_1") (pintype "unspecified"))
      (node (ref "U24") (pin "2") (pinfunction "2_2") (pintype "unspecified"))
    )
    (net (code "43") (name "Net-(D27-A)") (class "Default")
      (node (ref "D27") (pin "1") (pinfunction "A_1") (pintype "unspecified"))
      (node (ref "U23") (pin "2") (pinfunction "2_2") (pintype "unspecified"))
    )
    (net (code "44") (name "Net-(D28-A)") (class "Default")
      (node (ref "D28") (pin "1") (pinfunction "A_1") (pintype "unspecified"))
      (node (ref "U22") (pin "2") (pinfunction "2_2") (pintype "unspecified"))
    )
    (net (code "45") (name "Net-(D29-A)") (class "Default")
      (node (ref "D29") (pin "1") (pinfunction "A_1") (pintype "unspecified"))
      (node (ref "U21") (pin "2") (pinfunction "2_2") (pintype "unspecified"))
    )
    (net (code "46") (name "Net-(D30-A)") (class "Default")
      (node (ref "D30") (pin "1") (pinfunction "A_1") (pintype "unspecified"))
      (node (ref "U20") (pin "2") (pinfunction "2_2") (pintype "unspecified"))
    )
    (net (code "47") (name "Net-(D31-A)") (class "Default")
      (node (ref "D31") (pin "1") (pinfunction "A_1") (pintype "unspecified"))
      (node (ref "U19") (pin "2") (pinfunction "2_2") (pintype "unspecified"))
    )
    (net (code "48") (name "Net-(D32-A)") (class "Default")
      (node (ref "D32") (pin "1") (pinfunction "A_1") (pintype "unspecified"))
      (node (ref "U35") (pin "2") (pinfunction "2_2") (pintype "unspecified"))
    )
    (net (code "49") (name "Net-(D33-A)") (class "Default")
      (node (ref "D33") (pin "1") (pinfunction "A_1") (pintype "unspecified"))
      (node (ref "U36") (pin "2") (pinfunction "2_2") (pintype "unspecified"))
    )
    (net (code "50") (name "Net-(D34-A)") (class "Default")
      (node (ref "D34") (pin "1") (pinfunction "A_1") (pintype "unspecified"))
      (node (ref "U37") (pin "2") (pinfunction "2_2") (pintype "unspecified"))
    )
    (net (code "51") (name "Net-(D35-A)") (class "Default")
      (node (ref "D35") (pin "1") (pinfunction "A_1") (pintype "unspecified"))
      (node (ref "U38") (pin "2") (pinfunction "2_2") (pintype "unspecified"))
    )
    (net (code "52") (name "Net-(D36-A)") (class "Default")
      (node (ref "D36") (pin "1") (pinfunction "A_1") (pintype "unspecified"))
      (node (ref "U39") (pin "2") (pinfunction "2_2") (pintype "unspecified"))
    )
    (net (code "53") (name "Net-(D37-A)") (class "Default")
      (node (ref "D37") (pin "1") (pinfunction "A_1") (pintype "unspecified"))
      (node (ref "U40") (pin "2") (pinfunction "2_2") (pintype "unspecified"))
    )
    (net (code "54") (name "Net-(D38-A)") (class "Default")
      (node (ref "D38") (pin "1") (pinfunction "A_1") (pintype "unspecified"))
      (node (ref "U41") (pin "2") (pinfunction "2_2") (pintype "unspecified"))
    )
    (net (code "55") (name "Net-(D39-A)") (class "Default")
      (node (ref "D39") (pin "1") (pinfunction "A_1") (pintype "unspecified"))
      (node (ref "U42") (pin "2") (pinfunction "2_2") (pintype "unspecified"))
    )
    (net (code "56") (name "Net-(D40-A)") (class "Default")
      (node (ref "D40") (pin "1") (pinfunction "A_1") (pintype "unspecified"))
      (node (ref "U43") (pin "2") (pinfunction "2_2") (pintype "unspecified"))
    )
    (net (code "57") (name "Net-(D41-A)") (class "Default")
      (node (ref "D41") (pin "1") (pinfunction "A_1") (pintype "unspecified"))
      (node (ref "U44") (pin "2") (pinfunction "2_2") (pintype "unspecified"))
    )
    (net (code "58") (name "Net-(D42-A)") (class "Default")
      (node (ref "D42") (pin "1") (pinfunction "A_1") (pintype "unspecified"))
      (node (ref "U45") (pin "2") (pinfunction "2_2") (pintype "unspecified"))
    )
    (net (code "59") (name "Net-(D43-A)") (class "Default")
      (node (ref "D43") (pin "1") (pinfunction "A_1") (pintype "unspecified"))
      (node (ref "U46") (pin "2") (pinfunction "2_2") (pintype "unspecified"))
    )
    (net (code "60") (name "Net-(D44-A)") (class "Default")
      (node (ref "D44") (pin "1") (pinfunction "A_1") (pintype "unspecified"))
      (node (ref "U47") (pin "2") (pinfunction "2_2") (pintype "unspecified"))
    )
    (net (code "61") (name "Net-(D45-A)") (class "Default")
      (node (ref "D45") (pin "1") (pinfunction "A_1") (pintype "unspecified"))
      (node (ref "U48") (pin "2") (pinfunction "2_2") (pintype "unspecified"))
    )
    (net (code "62") (name "Net-(D46-A)") (class "Default")
      (node (ref "D46") (pin "1") (pinfunction "A_1") (pintype "unspecified"))
      (node (ref "U49") (pin "2") (pinfunction "2_2") (pintype "unspecified"))
    )
    (net (code "63") (name "Net-(D47-A)") (class "Default")
      (node (ref "D47") (pin "1") (pinfunction "A_1") (pintype "unspecified"))
      (node (ref "U51") (pin "2") (pinfunction "2_2") (pintype "unspecified"))
    )
    (net (code "64") (name "Net-(D48-A)") (class "Default")
      (node (ref "D48") (pin "1") (pinfunction "A_1") (pintype "unspecified"))
      (node (ref "U52") (pin "2") (pinfunction "2_2") (pintype "unspecified"))
    )
    (net (code "65") (name "Net-(D49-A)") (class "Default")
      (node (ref "D49") (pin "1") (pinfunction "A_1") (pintype "unspecified"))
      (node (ref "U53") (pin "2") (pinfunction "2_2") (pintype "unspecified"))
    )
    (net (code "66") (name "Net-(D50-A)") (class "Default")
      (node (ref "D50") (pin "1") (pinfunction "A_1") (pintype "unspecified"))
      (node (ref "U54") (pin "2") (pinfunction "2_2") (pintype "unspecified"))
    )
    (net (code "67") (name "Net-(D51-A)") (class "Default")
      (node (ref "D51") (pin "1") (pinfunction "A_1") (pintype "unspecified"))
      (node (ref "U55") (pin "2") (pinfunction "2_2") (pintype "unspecified"))
    )
    (net (code "68") (name "Net-(D52-A)") (class "Default")
      (node (ref "D52") (pin "1") (pinfunction "A_1") (pintype "unspecified"))
      (node (ref "U56") (pin "2") (pinfunction "2_2") (pintype "unspecified"))
    )
    (net (code "69") (name "Net-(D53-A)") (class "Default")
      (node (ref "D53") (pin "1") (pinfunction "A_1") (pintype "unspecified"))
      (node (ref "U57") (pin "2") (pinfunction "2_2") (pintype "unspecified"))
    )
    (net (code "70") (name "Net-(D54-A)") (class "Default")
      (node (ref "D54") (pin "1") (pinfunction "A_1") (pintype "unspecified"))
      (node (ref "U58") (pin "2") (pinfunction "2_2") (pintype "unspecified"))
    )
    (net (code "71") (name "Net-(D55-A)") (class "Default")
      (node (ref "D55") (pin "1") (pinfunction "A_1") (pintype "unspecified"))
      (node (ref "U59") (pin "2") (pinfunction "2_2") (pintype "unspecified"))
    )
    (net (code "72") (name "Net-(D56-A)") (class "Default")
      (node (ref "D56") (pin "1") (pinfunction "A_1") (pintype "unspecified"))
      (node (ref "U60") (pin "2") (pinfunction "2_2") (pintype "unspecified"))
    )
    (net (code "73") (name "Net-(D57-A)") (class "Default")
      (node (ref "D57") (pin "1") (pinfunction "A_1") (pintype "unspecified"))
      (node (ref "U61") (pin "2") (pinfunction "2_2") (pintype "unspecified"))
    )
    (net (code "74") (name "Net-(D58-A)") (class "Default")
      (node (ref "D58") (pin "1") (pinfunction "A_1") (pintype "unspecified"))
      (node (ref "U62") (pin "2") (pinfunction "2_2") (pintype "unspecified"))
    )
    (net (code "75") (name "Net-(D59-A)") (class "Default")
      (node (ref "D59") (pin "1") (pinfunction "A_1") (pintype "unspecified"))
      (node (ref "U63") (pin "2") (pinfunction "2_2") (pintype "unspecified"))
    )
    (net (code "76") (name "Net-(D60-A)") (class "Default")
      (node (ref "D60") (pin "1") (pinfunction "A_1") (pintype "unspecified"))
      (node (ref "U64") (pin "2") (pinfunction "2_2") (pintype "unspecified"))
    )
    (net (code "77") (name "Net-(D61-A)") (class "Default")
      (node (ref "D61") (pin "1") (pinfunction "A_1") (pintype "unspecified"))
      (node (ref "U80") (pin "2") (pinfunction "2_2") (pintype "unspecified"))
    )
    (net (code "78") (name "Net-(D62-A)") (class "Default")
      (node (ref "D62") (pin "1") (pinfunction "A_1") (pintype "unspecified"))
      (node (ref "U79") (pin "2") (pinfunction "2_2") (pintype "unspecified"))
    )
    (net (code "79") (name "Net-(D63-A)") (class "Default")
      (node (ref "D63") (pin "1") (pinfunction "A_1") (pintype "unspecified"))
      (node (ref "U78") (pin "2") (pinfunction "2_2") (pintype "unspecified"))
    )
    (net (code "80") (name "Net-(D64-A)") (class "Default")
      (node (ref "D64") (pin "1") (pinfunction "A_1") (pintype "unspecified"))
      (node (ref "U77") (pin "2") (pinfunction "2_2") (pintype "unspecified"))
    )
    (net (code "81") (name "Net-(D65-A)") (class "Default")
      (node (ref "D65") (pin "1") (pinfunction "A_1") (pintype "unspecified"))
      (node (ref "U76") (pin "2") (pinfunction "2_2") (pintype "unspecified"))
    )
    (net (code "82") (name "Net-(D66-A)") (class "Default")
      (node (ref "D66") (pin "1") (pinfunction "A_1") (pintype "unspecified"))
      (node (ref "U75") (pin "2") (pinfunction "2_2") (pintype "unspecified"))
    )
    (net (code "83") (name "Net-(D67-A)") (class "Default")
      (node (ref "D67") (pin "1") (pinfunction "A_1") (pintype "unspecified"))
      (node (ref "U74") (pin "2") (pinfunction "2_2") (pintype "unspecified"))
    )
    (net (code "84") (name "Net-(D68-A)") (class "Default")
      (node (ref "D68") (pin "1") (pinfunction "A_1") (pintype "unspecified"))
      (node (ref "U73") (pin "2") (pinfunction "2_2") (pintype "unspecified"))
    )
    (net (code "85") (name "Net-(D69-A)") (class "Default")
      (node (ref "D69") (pin "1") (pinfunction "A_1") (pintype "unspecified"))
      (node (ref "U72") (pin "2") (pinfunction "2_2") (pintype "unspecified"))
    )
    (net (code "86") (name "Net-(D70-A)") (class "Default")
      (node (ref "D70") (pin "1") (pinfunction "A_1") (pintype "unspecified"))
      (node (ref "U71") (pin "2") (pinfunction "2_2") (pintype "unspecified"))
    )
    (net (code "87") (name "Net-(D71-A)") (class "Default")
      (node (ref "D71") (pin "1") (pinfunction "A_1") (pintype "unspecified"))
      (node (ref "U70") (pin "2") (pinfunction "2_2") (pintype "unspecified"))
    )
    (net (code "88") (name "Net-(D72-A)") (class "Default")
      (node (ref "D72") (pin "1") (pinfunction "A_1") (pintype "unspecified"))
      (node (ref "U69") (pin "2") (pinfunction "2_2") (pintype "unspecified"))
    )
    (net (code "89") (name "Net-(D73-A)") (class "Default")
      (node (ref "D73") (pin "1") (pinfunction "A_1") (pintype "unspecified"))
      (node (ref "U68") (pin "2") (pinfunction "2_2") (pintype "unspecified"))
    )
    (net (code "90") (name "Net-(D74-A)") (class "Default")
      (node (ref "D74") (pin "1") (pinfunction "A_1") (pintype "unspecified"))
      (node (ref "U67") (pin "2") (pinfunction "2_2") (pintype "unspecified"))
    )
    (net (code "91") (name "Net-(D75-A)") (class "Default")
      (node (ref "D75") (pin "1") (pinfunction "A_1") (pintype "unspecified"))
      (node (ref "U98") (pin "2") (pinfunction "2_2") (pintype "unspecified"))
    )
    (net (code "92") (name "Net-(D76-A)") (class "Default")
      (node (ref "D76") (pin "1") (pinfunction "A_1") (pintype "unspecified"))
      (node (ref "U97") (pin "2") (pinfunction "2_2") (pintype "unspecified"))
    )
    (net (code "93") (name "Net-(D77-A)") (class "Default")
      (node (ref "D77") (pin "1") (pinfunction "A_1") (pintype "unspecified"))
      (node (ref "U96") (pin "2") (pinfunction "2_2") (pintype "unspecified"))
    )
    (net (code "94") (name "Net-(D78-A)") (class "Default")
      (node (ref "D78") (pin "1") (pinfunction "A_1") (pintype "unspecified"))
      (node (ref "U95") (pin "2") (pinfunction "2_2") (pintype "unspecified"))
    )
    (net (code "95") (name "Net-(D79-A)") (class "Default")
      (node (ref "D79") (pin "1") (pinfunction "A_1") (pintype "unspecified"))
      (node (ref "U94") (pin "2") (pinfunction "2_2") (pintype "unspecified"))
    )
    (net (code "96") (name "Net-(D80-A)") (class "Default")
      (node (ref "D80") (pin "1") (pinfunction "A_1") (pintype "unspecified"))
      (node (ref "U93") (pin "2") (pinfunction "2_2") (pintype "unspecified"))
    )
    (net (code "97") (name "Net-(D81-A)") (class "Default")
      (node (ref "D81") (pin "1") (pinfunction "A_1") (pintype "unspecified"))
      (node (ref "U86") (pin "2") (pinfunction "2_2") (pintype "unspecified"))
    )
    (net (code "98") (name "Net-(D82-A)") (class "Default")
      (node (ref "D82") (pin "1") (pinfunction "A_1") (pintype "unspecified"))
      (node (ref "U85") (pin "2") (pinfunction "2_2") (pintype "unspecified"))
    )
    (net (code "99") (name "Net-(D83-A)") (class "Default")
      (node (ref "D83") (pin "1") (pinfunction "A_1") (pintype "unspecified"))
      (node (ref "U84") (pin "2") (pinfunction "2_2") (pintype "unspecified"))
    )
    (net (code "100") (name "Net-(D84-A)") (class "Default")
      (node (ref "D84") (pin "1") (pinfunction "A_1") (pintype "unspecified"))
      (node (ref "U83") (pin "2") (pinfunction "2_2") (pintype "unspecified"))
    )
    (net (code "101") (name "Row0") (class "Default")
      (node (ref "D1") (pin "2") (pinfunction "K_2") (pintype "unspecified"))
      (node (ref "D10") (pin "2") (pinfunction "K_2") (pintype "unspecified"))
      (node (ref "D11") (pin "2") (pinfunction "K_2") (pintype "unspecified"))
      (node (ref "D12") (pin "2") (pinfunction "K_2") (pintype "unspecified"))
      (node (ref "D13") (pin "2") (pinfunction "K_2") (pintype "unspecified"))
      (node (ref "D14") (pin "2") (pinfunction "K_2") (pintype "unspecified"))
      (node (ref "D15") (pin "2") (pinfunction "K_2") (pintype "unspecified"))
      (node (ref "D16") (pin "2") (pinfunction "K_2") (pintype "unspecified"))
      (node (ref "D2") (pin "2") (pinfunction "K_2") (pintype "unspecified"))
      (node (ref "D3") (pin "2") (pinfunction "K_2") (pintype "unspecified"))
      (node (ref "D4") (pin "2") (pinfunction "K_2") (pintype "unspecified"))
      (node (ref "D5") (pin "2") (pinfunction "K_2") (pintype "unspecified"))
      (node (ref "D6") (pin "2") (pinfunction "K_2") (pintype "unspecified"))
      (node (ref "D7") (pin "2") (pinfunction "K_2") (pintype "unspecified"))
      (node (ref "D8") (pin "2") (pinfunction "K_2") (pintype "unspecified"))
      (node (ref "D9") (pin "2") (pinfunction "K_2") (pintype "unspecified"))
      (node (ref "FPC1") (pin "17") (pinfunction "17_17") (pintype "unspecified"))
    )
    (net (code "102") (name "Row1") (class "Default")
      (node (ref "D17") (pin "2") (pinfunction "K_2") (pintype "unspecified"))
      (node (ref "D18") (pin "2") (pinfunction "K_2") (pintype "unspecified"))
      (node (ref "D19") (pin "2") (pinfunction "K_2") (pintype "unspecified"))
      (node (ref "D20") (pin "2") (pinfunction "K_2") (pintype "unspecified"))
      (node (ref "D21") (pin "2") (pinfunction "K_2") (pintype "unspecified"))
      (node (ref "D22") (pin "2") (pinfunction "K_2") (pintype "unspecified"))
      (node (ref "D23") (pin "2") (pinfunction "K_2") (pintype "unspecified"))
      (node (ref "D24") (pin "2") (pinfunction "K_2") (pintype "unspecified"))
      (node (ref "D25") (pin "2") (pinfunction "K_2") (pintype "unspecified"))
      (node (ref "D26") (pin "2") (pinfunction "K_2") (pintype "unspecified"))
      (node (ref "D27") (pin "2") (pinfunction "K_2") (pintype "unspecified"))
      (node (ref "D28") (pin "2") (pinfunction "K_2") (pintype "unspecified"))
      (node (ref "D29") (pin "2") (pinfunction "K_2") (pintype "unspecified"))
      (node (ref "D30") (pin "2") (pinfunction "K_2") (pintype "unspecified"))
      (node (ref "D31") (pin "2") (pinfunction "K_2") (pintype "unspecified"))
      (node (ref "FPC1") (pin "18") (pinfunction "18_18") (pintype "unspecified"))
    )
    (net (code "103") (name "Row2") (class "Default")
      (node (ref "D32") (pin "2") (pinfunction "K_2") (pintype "unspecified"))
      (node (ref "D33") (pin "2") (pinfunction "K_2") (pintype "unspecified"))
      (node (ref "D34") (pin "2") (pinfunction "K_2") (pintype "unspecified"))
      (node (ref "D35") (pin "2") (pinfunction "K_2") (pintype "unspecified"))
      (node (ref "D36") (pin "2") (pinfunction "K_2") (pintype "unspecified"))
      (node (ref "D37") (pin "2") (pinfunction "K_2") (pintype "unspecified"))
      (node (ref "D38") (pin "2") (pinfunction "K_2") (pintype "unspecified"))
      (node (ref "D39") (pin "2") (pinfunction "K_2") (pintype "unspecified"))
      (node (ref "D40") (pin "2") (pinfunction "K_2") (pintype "unspecified"))
      (node (ref "D41") (pin "2") (pinfunction "K_2") (pintype "unspecified"))
      (node (ref "D42") (pin "2") (pinfunction "K_2") (pintype "unspecified"))
      (node (ref "D43") (pin "2") (pinfunction "K_2") (pintype "unspecified"))
      (node (ref "D44") (pin "2") (pinfunction "K_2") (pintype "unspecified"))
      (node (ref "D45") (pin "2") (pinfunction "K_2") (pintype "unspecified"))
      (node (ref "D46") (pin "2") (pinfunction "K_2") (pintype "unspecified"))
      (node (ref "FPC1") (pin "19") (pinfunction "19_19") (pintype "unspecified"))
    )
    (net (code "104") (name "Row3") (class "Default")
      (node (ref "D47") (pin "2") (pinfunction "K_2") (pintype "unspecified"))
      (node (ref "D48") (pin "2") (pinfunction "K_2") (pintype "unspecified"))
      (node (ref "D49") (pin "2") (pinfunction "K_2") (pintype "unspecified"))
      (node (ref "D50") (pin "2") (pinfunction "K_2") (pintype "unspecified"))
      (node (ref "D51") (pin "2") (pinfunction "K_2") (pintype "unspecified"))
      (node (ref "D52") (pin "2") (pinfunction "K_2") (pintype "unspecified"))
      (node (ref "D53") (pin "2") (pinfunction "K_2") (pintype "unspecified"))
      (node (ref "D54") (pin "2") (pinfunction "K_2") (pintype "unspecified"))
      (node (ref "D55") (pin "2") (pinfunction "K_2") (pintype "unspecified"))
      (node (ref "D56") (pin "2") (pinfunction "K_2") (pintype "unspecified"))
      (node (ref "D57") (pin "2") (pinfunction "K_2") (pintype "unspecified"))
      (node (ref "D58") (pin "2") (pinfunction "K_2") (pintype "unspecified"))
      (node (ref "D59") (pin "2") (pinfunction "K_2") (pintype "unspecified"))
      (node (ref "D60") (pin "2") (pinfunction "K_2") (pintype "unspecified"))
      (node (ref "FPC1") (pin "20") (pinfunction "20_20") (pintype "unspecified"))
    )
    (net (code "105") (name "Row4") (class "Default")
      (node (ref "D61") (pin "2") (pinfunction "K_2") (pintype "unspecified"))
      (node (ref "D62") (pin "2") (pinfunction "K_2") (pintype "unspecified"))
      (node (ref "D63") (pin "2") (pinfunction "K_2") (pintype "unspecified"))
      (node (ref "D64") (pin "2") (pinfunction "K_2") (pintype "unspecified"))
      (node (ref "D65") (pin "2") (pinfunction "K_2") (pintype "unspecified"))
      (node (ref "D66") (pin "2") (pinfunction "K_2") (pintype "unspecified"))
      (node (ref "D67") (pin "2") (pinfunction "K_2") (pintype "unspecified"))
      (node (ref "D68") (pin "2") (pinfunction "K_2") (pintype "unspecified"))
      (node (ref "D69") (pin "2") (pinfunction "K_2") (pintype "unspecified"))
      (node (ref "D70") (pin "2") (pinfunction "K_2") (pintype "unspecified"))
      (node (ref "D71") (pin "2") (pinfunction "K_2") (pintype "unspecified"))
      (node (ref "D72") (pin "2") (pinfunction "K_2") (pintype "unspecified"))
      (node (ref "D73") (pin "2") (pinfunction "K_2") (pintype "unspecified"))
      (node (ref "D74") (pin "2") (pinfunction "K_2") (pintype "unspecified"))
      (node (ref "FPC1") (pin "21") (pinfunction "21_21") (pintype "unspecified"))
    )
    (net (code "106") (name "Row5") (class "Default")
      (node (ref "D75") (pin "2") (pinfunction "K_2") (pintype "unspecified"))
      (node (ref "D76") (pin "2") (pinfunction "K_2") (pintype "unspecified"))
      (node (ref "D77") (pin "2") (pinfunction "K_2") (pintype "unspecified"))
      (node (ref "D78") (pin "2") (pinfunction "K_2") (pintype "unspecified"))
      (node (ref "D79") (pin "2") (pinfunction "K_2") (pintype "unspecified"))
      (node (ref "D80") (pin "2") (pinfunction "K_2") (pintype "unspecified"))
      (node (ref "D81") (pin "2") (pinfunction "K_2") (pintype "unspecified"))
      (node (ref "D82") (pin "2") (pinfunction "K_2") (pintype "unspecified"))
      (node (ref "D83") (pin "2") (pinfunction "K_2") (pintype "unspecified"))
      (node (ref "D84") (pin "2") (pinfunction "K_2") (pintype "unspecified"))
      (node (ref "FPC1") (pin "22") (pinfunction "22_22") (pintype "unspecified"))
    )
    (net (code "107") (name "unconnected-(FPC1-Pad23)") (class "Default")
      (node (ref "FPC1") (pin "23") (pinfunction "23_23") (pintype "unspecified+no_connect"))
    )
    (net (code "108") (name "unconnected-(FPC1-Pad24)") (class "Default")
      (node (ref "FPC1") (pin "24") (pinfunction "24_24") (pintype "unspecified+no_connect"))
    )
  )
)
